# EncoderArm_Photo.net
KiCad netlist of a schematic drawn in Altium Designer
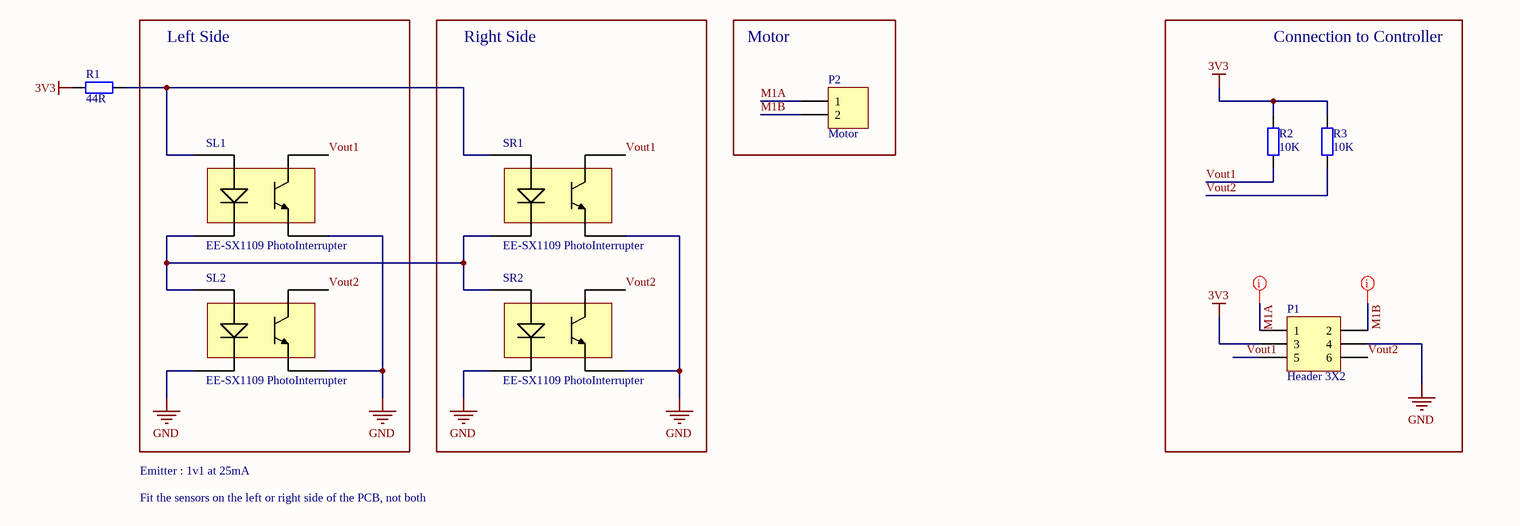
[diagram p0: EncoderArm_Photo.SchDoc]

(export (version "E")
  (design (tool "Eeschema 10.0.6"))
  (components
    (comp (ref "P1")
      (value "Header 3X2")
      (footprint "HDR2X3")
      (description "Header, 3-Pin, Dual row")
      (fields (field (name "PUBLISHER") "Altium Limited"))
      (libsource (lib "Miscellaneous Connectors") (part "Header 3X2"))
    )
    (comp (ref "P2")
      (value "Motor")
      (footprint "HDR1X2")
      (description "Header, 2-Pin")
      (fields (field (name "PUBLISHER") "Altium Limited"))
      (libsource (lib "Miscellaneous Connectors") (part "Header 2"))
    )
    (comp (ref "R1")
      (value "44R")
      (footprint "6-0805_M")
      (description "Resistor")
      (fields (field (name "Comment") "Res2") (field (name "PUBLISHER") "Altium Limited"))
      (libsource (lib "Miscellaneous Devices") (part "Res2"))
    )
    (comp (ref "R2")
      (value "10K")
      (footprint "6-0805_M")
      (description "Resistor")
      (fields (field (name "Comment") "Res2") (field (name "PUBLISHER") "Altium Limited"))
      (libsource (lib "") (part "Res2_1"))
    )
    (comp (ref "R3")
      (value "10K")
      (footprint "6-0805_M")
      (description "Resistor")
      (fields (field (name "Comment") "Res2") (field (name "PUBLISHER") "Altium Limited"))
      (libsource (lib "") (part "Res2_1"))
    )
    (comp (ref "SL1")
      (value "EE-SX1109 PhotoInterrupter")
      (footprint "EE-SX1109")
      (libsource (lib "PenguinPi_v2") (part "EE-SX1109 PhotoInterrupter"))
    )
    (comp (ref "SL2")
      (value "EE-SX1109 PhotoInterrupter")
      (footprint "EE-SX1109")
      (libsource (lib "PenguinPi_v2") (part "EE-SX1109 PhotoInterrupter"))
    )
    (comp (ref "SR1")
      (value "EE-SX1109 PhotoInterrupter")
      (footprint "EE-SX1109")
      (libsource (lib "PenguinPi_v2") (part "EE-SX1109 PhotoInterrupter"))
    )
    (comp (ref "SR2")
      (value "EE-SX1109 PhotoInterrupter")
      (footprint "EE-SX1109")
      (libsource (lib "PenguinPi_v2") (part "EE-SX1109 PhotoInterrupter"))
    )
  )
  (nets
    (net (code "1") (name "/M1A") (class "Default")
      (node (ref "P1") (pin "1") (pinfunction "1_1") (pintype "passive"))
      (node (ref "P2") (pin "1") (pinfunction "1_1") (pintype "passive"))
    )
    (net (code "2") (name "/M1B") (class "Default")
      (node (ref "P1") (pin "2") (pinfunction "2_2") (pintype "passive"))
      (node (ref "P2") (pin "2") (pinfunction "2_2") (pintype "passive"))
    )
    (net (code "3") (name "/Vout1") (class "Default")
      (node (ref "P1") (pin "5") (pinfunction "5_5") (pintype "passive"))
      (node (ref "R2") (pin "1") (pinfunction "1_1") (pintype "passive"))
      (node (ref "SL1") (pin "3") (pinfunction "C_3") (pintype "passive"))
      (node (ref "SR1") (pin "3") (pinfunction "C_3") (pintype "passive"))
    )
    (net (code "4") (name "/Vout2") (class "Default")
      (node (ref "P1") (pin "6") (pinfunction "6_6") (pintype "passive"))
      (node (ref "R3") (pin "1") (pinfunction "1_1") (pintype "passive"))
      (node (ref "SL2") (pin "3") (pinfunction "C_3") (pintype "passive"))
      (node (ref "SR2") (pin "3") (pinfunction "C_3") (pintype "passive"))
    )
    (net (code "5") (name "3V3") (class "Default")
      (node (ref "P1") (pin "3") (pinfunction "3_3") (pintype "passive"))
      (node (ref "R1") (pin "2") (pinfunction "2_2") (pintype "passive"))
      (node (ref "R2") (pin "2") (pinfunction "2_2") (pintype "passive"))
      (node (ref "R3") (pin "2") (pinfunction "2_2") (pintype "passive"))
    )
    (net (code "6") (name "GND") (class "Default")
      (node (ref "P1") (pin "4") (pinfunction "4_4") (pintype "passive"))
      (node (ref "SL1") (pin "2") (pinfunction "E_2") (pintype "passive"))
      (node (ref "SL2") (pin "1") (pinfunction "K_1") (pintype "passive"))
      (node (ref "SL2") (pin "2") (pinfunction "E_2") (pintype "passive"))
      (node (ref "SR1") (pin "2") (pinfunction "E_2") (pintype "passive"))
      (node (ref "SR2") (pin "1") (pinfunction "K_1") (pintype "passive"))
      (node (ref "SR2") (pin "2") (pinfunction "E_2") (pintype "passive"))
    )
    (net (code "7") (name "Net-(SL1-A)") (class "Default")
      (node (ref "R1") (pin "1") (pinfunction "1_1") (pintype "passive"))
      (node (ref "SL1") (pin "4") (pinfunction "A_4") (pintype "passive"))
      (node (ref "SR1") (pin "4") (pinfunction "A_4") (pintype "passive"))
    )
    (net (code "8") (name "Net-(SL1-K)") (class "Default")
      (node (ref "SL1") (pin "1") (pinfunction "K_1") (pintype "passive"))
      (node (ref "SL2") (pin "4") (pinfunction "A_4") (pintype "passive"))
      (node (ref "SR1") (pin "1") (pinfunction "K_1") (pintype "passive"))
      (node (ref "SR2") (pin "4") (pinfunction "A_4") (pintype "passive"))
    )
  )
)
